# LED_Driver.net
KiCad netlist of a schematic drawn in EAGLE
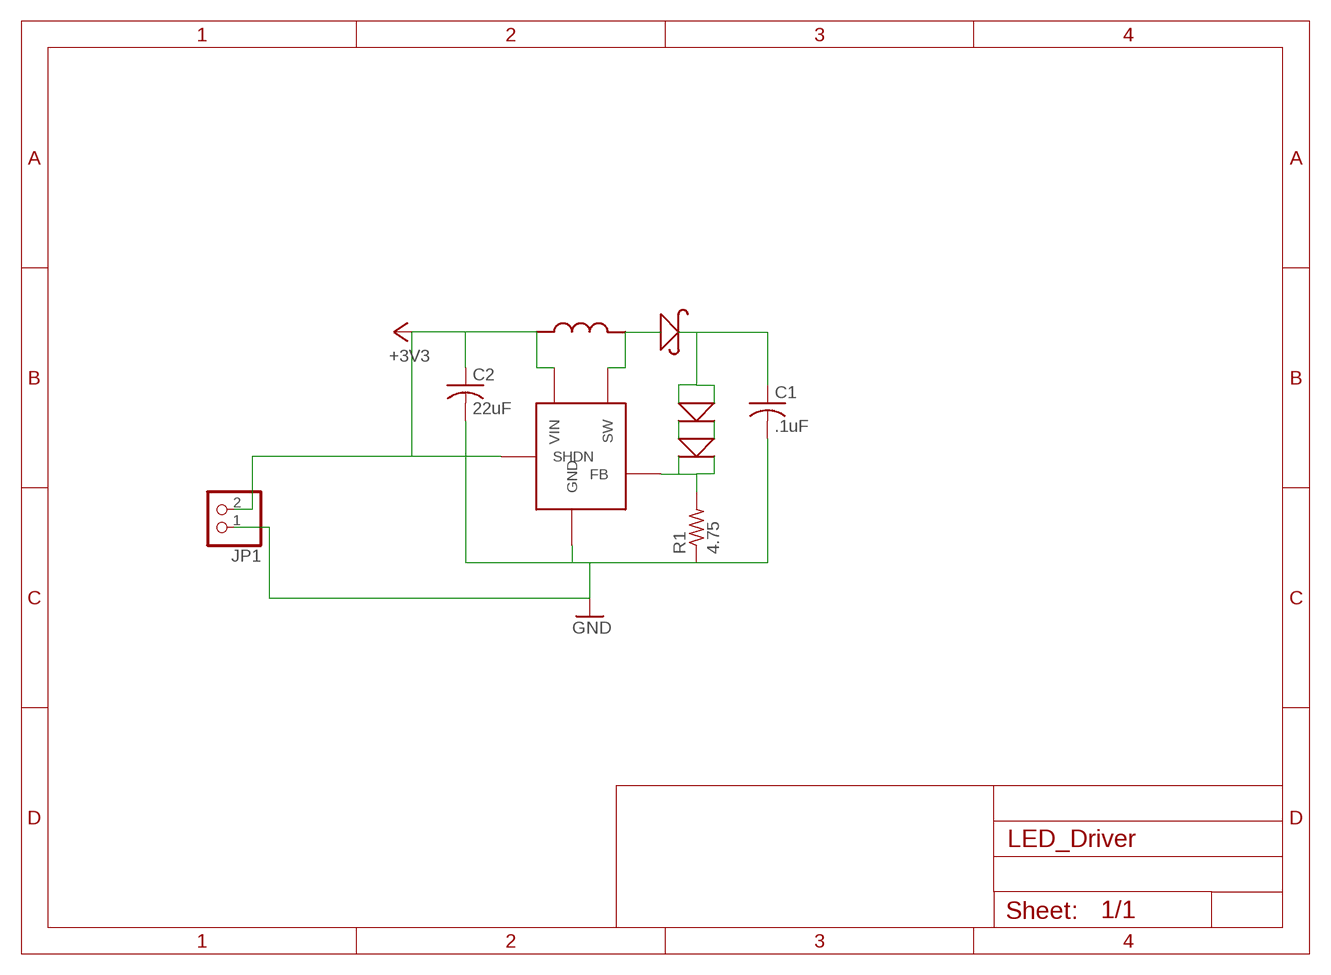
[diagram p0: schematic, sheet 1]

(export (version "E")
  (design (tool "Eeschema 10.0.6"))
  (components
    (comp (ref "C1")
      (value ".1uF")
      (footprint "eagle-import:C0603")
      (libsource (lib "eagle-import") (part "C-USC0603"))
    )
    (comp (ref "C2")
      (value "22uF")
      (footprint "eagle-import:C0603")
      (libsource (lib "eagle-import") (part "C-USC0603"))
    )
    (comp (ref "JP1")
      (value "PINHD-1X2")
      (footprint "eagle-import:1X02")
      (libsource (lib "eagle-import") (part "PINHD-1X2"))
    )
    (comp (ref "R1")
      (value "4.75")
      (footprint "eagle-import:R0603")
      (libsource (lib "eagle-import") (part "R-US_R0603"))
    )
    (comp (ref "U$1")
      (value "LT1937")
      (footprint "eagle-import:TSOT-23")
      (libsource (lib "eagle-import") (part "LT1937"))
    )
    (comp (ref "U$2")
      (value "NLCV25-PF")
      (footprint "eagle-import:NLCV25-PF")
      (libsource (lib "eagle-import") (part "NLCV25-PF"))
    )
    (comp (ref "U$3")
      (value "DB2J310")
      (footprint "eagle-import:DB2J310")
      (libsource (lib "eagle-import") (part "DB2J310"))
    )
    (comp (ref "U$4")
      (value "CLA2A-WKW-CYBZ0343CT")
      (footprint "eagle-import:CLA2A-WKW-CYBZ0343CT")
      (libsource (lib "eagle-import") (part "CLA2A-WKW-CYBZ0343CT"))
    )
    (comp (ref "U$5")
      (value "CLA2A-WKW-CYBZ0343CT")
      (footprint "eagle-import:CLA2A-WKW-CYBZ0343CT")
      (libsource (lib "eagle-import") (part "CLA2A-WKW-CYBZ0343CT"))
    )
  )
  (nets
    (net (code "1") (name "+3V3") (class "Default")
      (node (ref "C2") (pin "1") (pinfunction "1_1") (pintype "passive"))
      (node (ref "JP1") (pin "2") (pinfunction "2_2") (pintype "passive"))
      (node (ref "U$1") (pin "P$4") (pinfunction "SHDN_P$4") (pintype "bidirectional"))
      (node (ref "U$1") (pin "P$5") (pinfunction "VIN_P$5") (pintype "bidirectional"))
      (node (ref "U$2") (pin "P$1") (pinfunction "P$1_P$1") (pintype "bidirectional"))
    )
    (net (code "2") (name "GND") (class "Default")
      (node (ref "C1") (pin "2") (pinfunction "2_2") (pintype "passive"))
      (node (ref "C2") (pin "2") (pinfunction "2_2") (pintype "passive"))
      (node (ref "JP1") (pin "1") (pinfunction "1_1") (pintype "passive"))
      (node (ref "R1") (pin "1") (pinfunction "1_1") (pintype "passive"))
      (node (ref "U$1") (pin "P$2") (pinfunction "GND_P$2") (pintype "bidirectional"))
    )
    (net (code "3") (name "Net-(U$1-FB)") (class "Default")
      (node (ref "R1") (pin "2") (pinfunction "2_2") (pintype "passive"))
      (node (ref "U$1") (pin "P$3") (pinfunction "FB_P$3") (pintype "bidirectional"))
      (node (ref "U$5") (pin "P$3") (pinfunction "GND1_P$3") (pintype "bidirectional"))
      (node (ref "U$5") (pin "P$4") (pinfunction "GND2_P$4") (pintype "bidirectional"))
    )
    (net (code "4") (name "Net-(U$1-SW)") (class "Default")
      (node (ref "U$1") (pin "P$1") (pinfunction "SW_P$1") (pintype "bidirectional"))
      (node (ref "U$2") (pin "P$2") (pinfunction "P$2_P$2") (pintype "bidirectional"))
      (node (ref "U$3") (pin "P$2") (pinfunction "VIN_P$2") (pintype "bidirectional"))
    )
    (net (code "5") (name "Net-(U$3-GND)") (class "Default")
      (node (ref "C1") (pin "1") (pinfunction "1_1") (pintype "passive"))
      (node (ref "U$3") (pin "P$1") (pinfunction "GND_P$1") (pintype "bidirectional"))
      (node (ref "U$4") (pin "P$1") (pinfunction "VIN1_P$1") (pintype "bidirectional"))
      (node (ref "U$4") (pin "P$2") (pinfunction "VIN2_P$2") (pintype "bidirectional"))
    )
    (net (code "6") (name "Net-(U$4-GND1)") (class "Default")
      (node (ref "U$4") (pin "P$3") (pinfunction "GND1_P$3") (pintype "bidirectional"))
      (node (ref "U$5") (pin "P$1") (pinfunction "VIN1_P$1") (pintype "bidirectional"))
    )
    (net (code "7") (name "Net-(U$4-GND2)") (class "Default")
      (node (ref "U$4") (pin "P$4") (pinfunction "GND2_P$4") (pintype "bidirectional"))
      (node (ref "U$5") (pin "P$2") (pinfunction "VIN2_P$2") (pintype "bidirectional"))
    )
  )
)
